# HVPulser0_3UCC21520.net
KiCad netlist of a schematic drawn in EAGLE
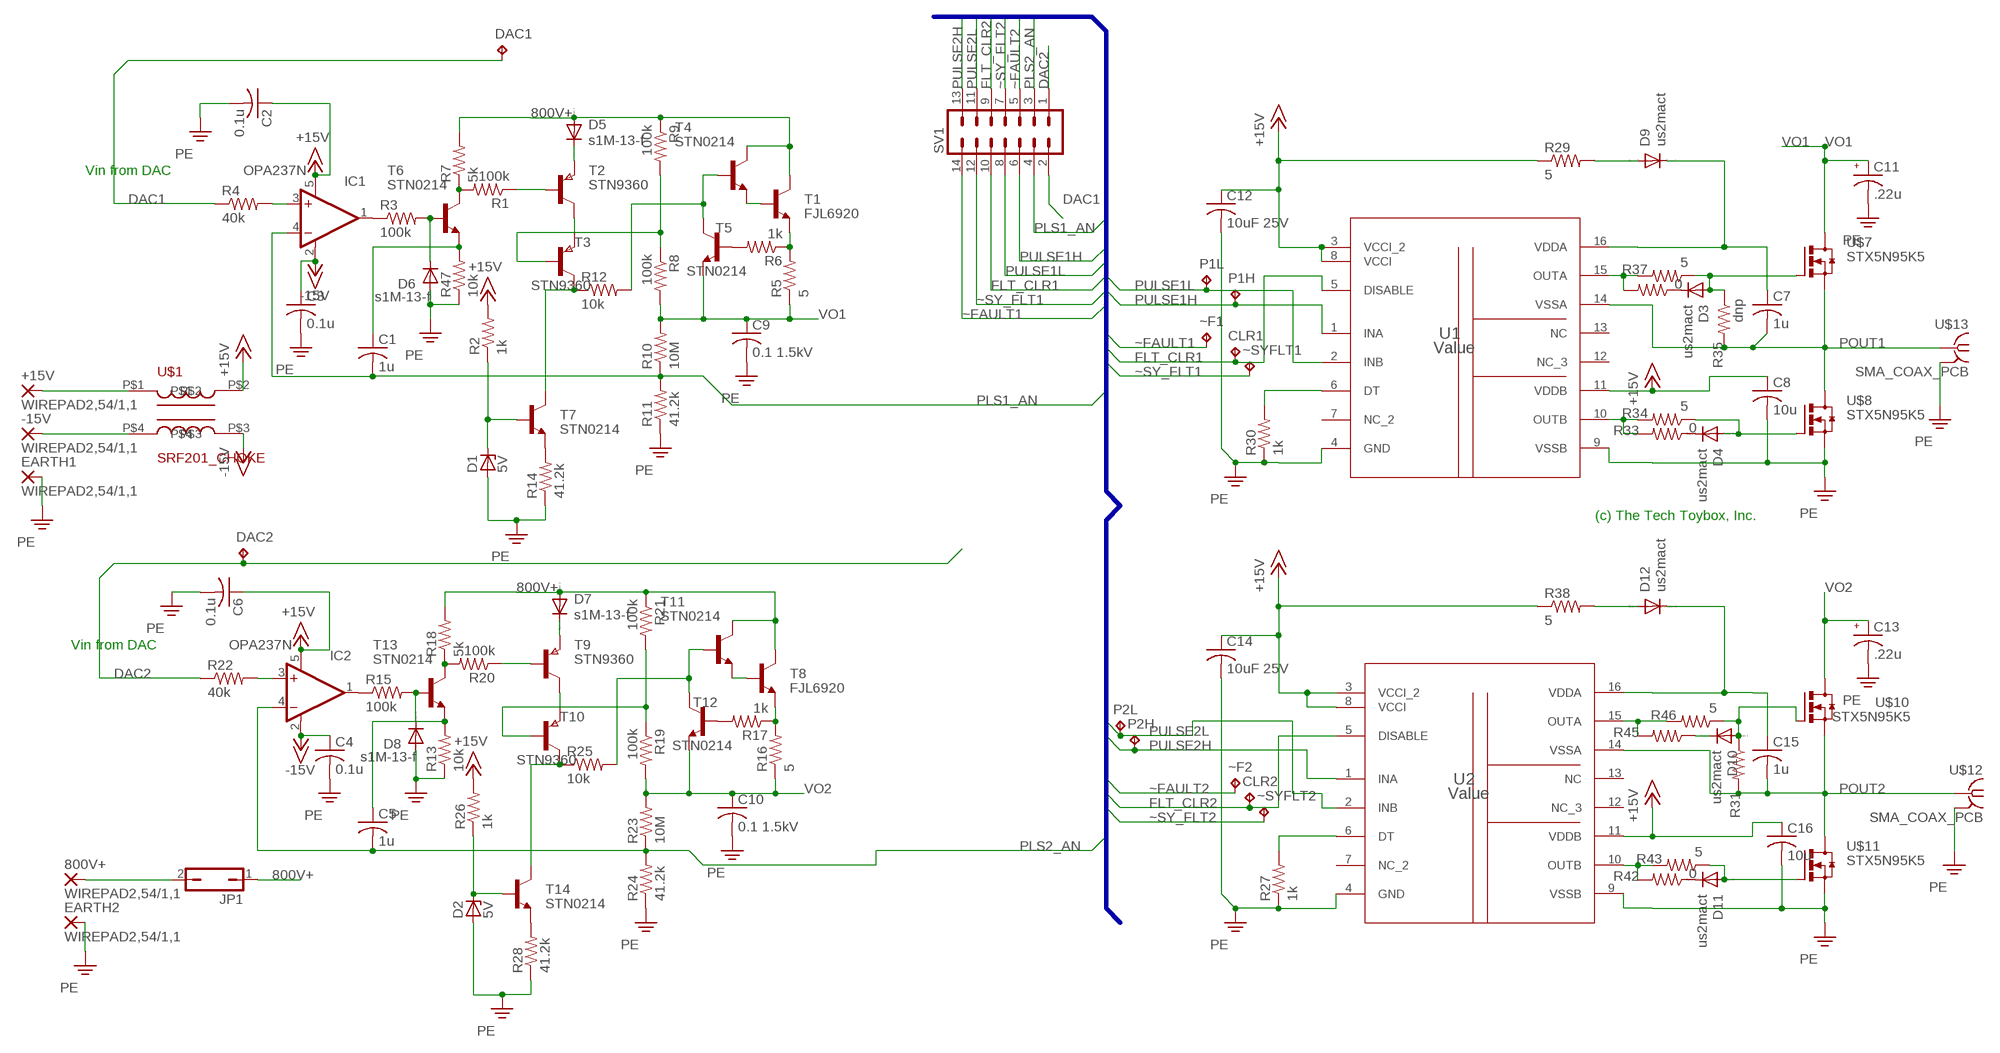
[diagram p0: schematic, sheet 1]

(export (version "E")
  (design (tool "Eeschema 10.0.6"))
  (components
    (comp (ref "+15V")
      (value "WIREPAD2,54/1,1")
      (footprint "eagle-import:2,54_1,1")
      (libsource (lib "eagle-import") (part "WIREPAD2,54/1,1"))
    )
    (comp (ref "-15V")
      (value "WIREPAD2,54/1,1")
      (footprint "eagle-import:2,54_1,1")
      (libsource (lib "eagle-import") (part "WIREPAD2,54/1,1"))
    )
    (comp (ref "800V+")
      (value "WIREPAD2,54/1,1")
      (footprint "eagle-import:2,54_1,1")
      (libsource (lib "eagle-import") (part "WIREPAD2,54/1,1"))
    )
    (comp (ref "C1")
      (value "1u")
      (footprint "eagle-import:C0805")
      (libsource (lib "eagle-import") (part "rcl_C-USC0805"))
    )
    (comp (ref "C2")
      (value "0.1u")
      (footprint "eagle-import:C0805")
      (libsource (lib "eagle-import") (part "rcl_C-USC0805"))
    )
    (comp (ref "C3")
      (value "0.1u")
      (footprint "eagle-import:C0805")
      (libsource (lib "eagle-import") (part "rcl_C-USC0805"))
    )
    (comp (ref "C4")
      (value "0.1u")
      (footprint "eagle-import:C0805")
      (libsource (lib "eagle-import") (part "rcl_C-USC0805"))
    )
    (comp (ref "C5")
      (value "1u")
      (footprint "eagle-import:C0805")
      (libsource (lib "eagle-import") (part "rcl_C-USC0805"))
    )
    (comp (ref "C6")
      (value "0.1u")
      (footprint "eagle-import:C0805")
      (libsource (lib "eagle-import") (part "rcl_C-USC0805"))
    )
    (comp (ref "C7")
      (value "1u")
      (footprint "eagle-import:C0805")
      (libsource (lib "eagle-import") (part "rcl_C-USC0805"))
    )
    (comp (ref "C8")
      (value "10u")
      (footprint "eagle-import:C1210")
      (libsource (lib "eagle-import") (part "rcl_C-USC1210"))
    )
    (comp (ref "C9")
      (value "0.1 1.5kV")
      (footprint "eagle-import:C2225K")
      (libsource (lib "eagle-import") (part "rcl_C-USC2225K"))
    )
    (comp (ref "C10")
      (value "0.1 1.5kV")
      (footprint "eagle-import:C2225K")
      (libsource (lib "eagle-import") (part "rcl_C-USC2225K"))
    )
    (comp (ref "C11")
      (value ".22u")
      (footprint "eagle-import:C050-035X075")
      (fields (field (name "PARTNO") "C1608X7R1H224K080AB"))
      (libsource (lib "eagle-import") (part "C-US050-035X075"))
    )
    (comp (ref "C12")
      (value "10uF 25V")
      (footprint "eagle-import:C0805")
      (libsource (lib "eagle-import") (part "rcl_C-USC0805"))
    )
    (comp (ref "C13")
      (value ".22u")
      (footprint "eagle-import:C050-035X075")
      (fields (field (name "PARTNO") "C1608X7R1H224K080AB"))
      (libsource (lib "eagle-import") (part "C-US050-035X075"))
    )
    (comp (ref "C14")
      (value "10uF 25V")
      (footprint "eagle-import:C0805")
      (libsource (lib "eagle-import") (part "rcl_C-USC0805"))
    )
    (comp (ref "C15")
      (value "1u")
      (footprint "eagle-import:C0805")
      (libsource (lib "eagle-import") (part "rcl_C-USC0805"))
    )
    (comp (ref "C16")
      (value "10u")
      (footprint "eagle-import:C1210")
      (libsource (lib "eagle-import") (part "rcl_C-USC1210"))
    )
    (comp (ref "CLR1")
      (value "TPTP10R")
      (footprint "eagle-import:TP10R")
      (libsource (lib "eagle-import") (part "TPTP10R"))
    )
    (comp (ref "CLR2")
      (value "TPTP10R")
      (footprint "eagle-import:TP10R")
      (libsource (lib "eagle-import") (part "TPTP10R"))
    )
    (comp (ref "D1")
      (value "5V")
      (footprint "eagle-import:DO41Z10")
      (libsource (lib "eagle-import") (part "ZENER-DIODEDO41Z10"))
    )
    (comp (ref "D2")
      (value "5V")
      (footprint "eagle-import:DO41Z10")
      (libsource (lib "eagle-import") (part "ZENER-DIODEDO41Z10"))
    )
    (comp (ref "D3")
      (value "us2mact")
      (footprint "eagle-import:DO214AC")
      (libsource (lib "eagle-import") (part "DIODE-DO214AC"))
    )
    (comp (ref "D4")
      (value "us2mact")
      (footprint "eagle-import:DO214AC")
      (libsource (lib "eagle-import") (part "DIODE-DO214AC"))
    )
    (comp (ref "D5")
      (value "s1M-13-f")
      (footprint "eagle-import:DO214AC")
      (libsource (lib "eagle-import") (part "DIODE-DO214AC"))
    )
    (comp (ref "D6")
      (value "s1M-13-f")
      (footprint "eagle-import:DO214AC")
      (libsource (lib "eagle-import") (part "DIODE-DO214AC"))
    )
    (comp (ref "D7")
      (value "s1M-13-f")
      (footprint "eagle-import:DO214AC")
      (libsource (lib "eagle-import") (part "DIODE-DO214AC"))
    )
    (comp (ref "D8")
      (value "s1M-13-f")
      (footprint "eagle-import:DO214AC")
      (libsource (lib "eagle-import") (part "DIODE-DO214AC"))
    )
    (comp (ref "D9")
      (value "us2mact")
      (footprint "eagle-import:DO214AC")
      (libsource (lib "eagle-import") (part "DIODE-DO214AC"))
    )
    (comp (ref "D10")
      (value "us2mact")
      (footprint "eagle-import:DO214AC")
      (libsource (lib "eagle-import") (part "DIODE-DO214AC"))
    )
    (comp (ref "D11")
      (value "us2mact")
      (footprint "eagle-import:DO214AC")
      (libsource (lib "eagle-import") (part "DIODE-DO214AC"))
    )
    (comp (ref "D12")
      (value "us2mact")
      (footprint "eagle-import:DO214AC")
      (libsource (lib "eagle-import") (part "DIODE-DO214AC"))
    )
    (comp (ref "DAC1")
      (value "TPTP10R")
      (footprint "eagle-import:TP10R")
      (libsource (lib "eagle-import") (part "TPTP10R"))
    )
    (comp (ref "DAC2")
      (value "TPTP10R")
      (footprint "eagle-import:TP10R")
      (libsource (lib "eagle-import") (part "TPTP10R"))
    )
    (comp (ref "EARTH1")
      (value "WIREPAD2,54/1,1")
      (footprint "eagle-import:2,54_1,1")
      (libsource (lib "eagle-import") (part "WIREPAD2,54/1,1"))
    )
    (comp (ref "EARTH2")
      (value "WIREPAD2,54/1,1")
      (footprint "eagle-import:2,54_1,1")
      (libsource (lib "eagle-import") (part "WIREPAD2,54/1,1"))
    )
    (comp (ref "IC1")
      (value "OPA237N")
      (footprint "eagle-import:SOT23-5")
      (fields (field (name "MF") "TEXAS INSTRUMENTS") (field (name "MPN") "OPA237NA/250"))
      (libsource (lib "eagle-import") (part "OPA237N"))
    )
    (comp (ref "IC2")
      (value "OPA237N")
      (footprint "eagle-import:SOT23-5")
      (fields (field (name "MF") "TEXAS INSTRUMENTS") (field (name "MPN") "OPA237NA/250"))
      (libsource (lib "eagle-import") (part "OPA237N"))
    )
    (comp (ref "JP1")
      (value "JP1Q")
      (footprint "eagle-import:JP1")
      (libsource (lib "eagle-import") (part "JP1Q"))
    )
    (comp (ref "P1H")
      (value "TPTP10R")
      (footprint "eagle-import:TP10R")
      (libsource (lib "eagle-import") (part "TPTP10R"))
    )
    (comp (ref "P1L")
      (value "TPTP10R")
      (footprint "eagle-import:TP10R")
      (libsource (lib "eagle-import") (part "TPTP10R"))
    )
    (comp (ref "P2H")
      (value "TPTP10R")
      (footprint "eagle-import:TP10R")
      (libsource (lib "eagle-import") (part "TPTP10R"))
    )
    (comp (ref "P2L")
      (value "TPTP10R")
      (footprint "eagle-import:TP10R")
      (libsource (lib "eagle-import") (part "TPTP10R"))
    )
    (comp (ref "R1")
      (value "100k")
      (footprint "eagle-import:P0613_15")
      (libsource (lib "eagle-import") (part "R-US_0613/15"))
    )
    (comp (ref "R2")
      (value "1k")
      (footprint "eagle-import:P0613_15")
      (libsource (lib "eagle-import") (part "R-US_0613/15"))
    )
    (comp (ref "R3")
      (value "100k")
      (footprint "eagle-import:R0603")
      (libsource (lib "eagle-import") (part "R-US_R0603"))
    )
    (comp (ref "R4")
      (value "40k")
      (footprint "eagle-import:R0603")
      (libsource (lib "eagle-import") (part "R-US_R0603"))
    )
    (comp (ref "R5")
      (value "5")
      (footprint "eagle-import:P0613_15")
      (libsource (lib "eagle-import") (part "R-US_0613/15"))
    )
    (comp (ref "R6")
      (value "1k")
      (footprint "eagle-import:P0613_15")
      (libsource (lib "eagle-import") (part "R-US_0613/15"))
    )
    (comp (ref "R7")
      (value "5k")
      (footprint "eagle-import:R0603")
      (libsource (lib "eagle-import") (part "R-US_R0603"))
    )
    (comp (ref "R8")
      (value "100k")
      (footprint "eagle-import:P0613_15")
      (libsource (lib "eagle-import") (part "R-US_0613/15"))
    )
    (comp (ref "R9")
      (value "100k")
      (footprint "eagle-import:P0613_15")
      (libsource (lib "eagle-import") (part "R-US_0613/15"))
    )
    (comp (ref "R10")
      (value "10M")
      (footprint "eagle-import:P0613_15")
      (libsource (lib "eagle-import") (part "R-US_0613/15"))
    )
    (comp (ref "R11")
      (value "41.2k")
      (footprint "eagle-import:P0613_15")
      (libsource (lib "eagle-import") (part "R-US_0613/15"))
    )
    (comp (ref "R12")
      (value "10k")
      (footprint "eagle-import:R0603")
      (libsource (lib "eagle-import") (part "R-US_R0603"))
    )
    (comp (ref "R13")
      (value "10k")
      (footprint "eagle-import:R0805")
      (libsource (lib "eagle-import") (part "R-US_R0805"))
    )
    (comp (ref "R14")
      (value "41.2k")
      (footprint "eagle-import:P0613_15")
      (libsource (lib "eagle-import") (part "R-US_0613/15"))
    )
    (comp (ref "R15")
      (value "100k")
      (footprint "eagle-import:R0603")
      (libsource (lib "eagle-import") (part "R-US_R0603"))
    )
    (comp (ref "R16")
      (value "5")
      (footprint "eagle-import:P0613_15")
      (libsource (lib "eagle-import") (part "R-US_0613/15"))
    )
    (comp (ref "R17")
      (value "1k")
      (footprint "eagle-import:P0613_15")
      (libsource (lib "eagle-import") (part "R-US_0613/15"))
    )
    (comp (ref "R18")
      (value "5k")
      (footprint "eagle-import:R0603")
      (libsource (lib "eagle-import") (part "R-US_R0603"))
    )
    (comp (ref "R19")
      (value "100k")
      (footprint "eagle-import:P0613_15")
      (libsource (lib "eagle-import") (part "R-US_0613/15"))
    )
    (comp (ref "R20")
      (value "100k")
      (footprint "eagle-import:P0613_15")
      (libsource (lib "eagle-import") (part "R-US_0613/15"))
    )
    (comp (ref "R21")
      (value "100k")
      (footprint "eagle-import:P0613_15")
      (libsource (lib "eagle-import") (part "R-US_0613/15"))
    )
    (comp (ref "R22")
      (value "40k")
      (footprint "eagle-import:R0603")
      (libsource (lib "eagle-import") (part "R-US_R0603"))
    )
    (comp (ref "R23")
      (value "10M")
      (footprint "eagle-import:P0613_15")
      (libsource (lib "eagle-import") (part "R-US_0613/15"))
    )
    (comp (ref "R24")
      (value "41.2k")
      (footprint "eagle-import:P0613_15")
      (libsource (lib "eagle-import") (part "R-US_0613/15"))
    )
    (comp (ref "R25")
      (value "10k")
      (footprint "eagle-import:R0603")
      (libsource (lib "eagle-import") (part "R-US_R0603"))
    )
    (comp (ref "R26")
      (value "1k")
      (footprint "eagle-import:P0613_15")
      (libsource (lib "eagle-import") (part "R-US_0613/15"))
    )
    (comp (ref "R27")
      (value "1k")
      (footprint "eagle-import:R0805")
      (libsource (lib "eagle-import") (part "R-US_R0805"))
    )
    (comp (ref "R28")
      (value "41.2k")
      (footprint "eagle-import:P0613_15")
      (libsource (lib "eagle-import") (part "R-US_0613/15"))
    )
    (comp (ref "R29")
      (value "5")
      (footprint "eagle-import:0207_10")
      (libsource (lib "eagle-import") (part "R-US_0207/10"))
    )
    (comp (ref "R30")
      (value "1k")
      (footprint "eagle-import:R0805")
      (libsource (lib "eagle-import") (part "R-US_R0805"))
    )
    (comp (ref "R31")
      (value "15")
      (footprint "eagle-import:R0805")
      (libsource (lib "eagle-import") (part "R-US_R0805"))
    )
    (comp (ref "R33")
      (value "0")
      (footprint "eagle-import:R0805")
      (libsource (lib "eagle-import") (part "R-US_R0805"))
    )
    (comp (ref "R34")
      (value "5")
      (footprint "eagle-import:R0805")
      (libsource (lib "eagle-import") (part "R-US_R0805"))
    )
    (comp (ref "R35")
      (value "dnp")
      (footprint "eagle-import:R0805")
      (libsource (lib "eagle-import") (part "R-US_R0805"))
    )
    (comp (ref "R36")
      (value "0")
      (footprint "eagle-import:R0805")
      (libsource (lib "eagle-import") (part "R-US_R0805"))
    )
    (comp (ref "R37")
      (value "5")
      (footprint "eagle-import:R0805")
      (libsource (lib "eagle-import") (part "R-US_R0805"))
    )
    (comp (ref "R38")
      (value "5")
      (footprint "eagle-import:0207_10")
      (libsource (lib "eagle-import") (part "R-US_0207/10"))
    )
    (comp (ref "R42")
      (value "0")
      (footprint "eagle-import:R0805")
      (libsource (lib "eagle-import") (part "R-US_R0805"))
    )
    (comp (ref "R43")
      (value "5")
      (footprint "eagle-import:R0805")
      (libsource (lib "eagle-import") (part "R-US_R0805"))
    )
    (comp (ref "R45")
      (value "15")
      (footprint "eagle-import:R0805")
      (libsource (lib "eagle-import") (part "R-US_R0805"))
    )
    (comp (ref "R46")
      (value "5")
      (footprint "eagle-import:R0805")
      (libsource (lib "eagle-import") (part "R-US_R0805"))
    )
    (comp (ref "R47")
      (value "10k")
      (footprint "eagle-import:R0805")
      (libsource (lib "eagle-import") (part "R-US_R0805"))
    )
    (comp (ref "SV1")
      (value "MA07-2")
      (footprint "eagle-import:MA07-2")
      (libsource (lib "eagle-import") (part "MA07-2"))
    )
    (comp (ref "T1")
      (value "FJL6920")
      (footprint "eagle-import:TO264V")
      (libsource (lib "eagle-import") (part "FJL6920-NPN_POWER"))
    )
    (comp (ref "T2")
      (value "STN9360")
      (footprint "eagle-import:SOT223")
      (fields (field (name "MPN") "DJT4030P-13"))
      (libsource (lib "eagle-import") (part "PNPSOT223"))
    )
    (comp (ref "T3")
      (value "STN9360")
      (footprint "eagle-import:SOT223")
      (fields (field (name "MPN") "DJT4030P-13"))
      (libsource (lib "eagle-import") (part "PNPSOT223"))
    )
    (comp (ref "T4")
      (value "STN0214")
      (footprint "eagle-import:SOT223")
      (libsource (lib "eagle-import") (part "-NPN-SOT223"))
    )
    (comp (ref "T5")
      (value "STN0214")
      (footprint "eagle-import:SOT223")
      (libsource (lib "eagle-import") (part "-NPN-SOT223"))
    )
    (comp (ref "T6")
      (value "STN0214")
      (footprint "eagle-import:SOT223")
      (libsource (lib "eagle-import") (part "-NPN-SOT223"))
    )
    (comp (ref "T7")
      (value "STN0214")
      (footprint "eagle-import:SOT223")
      (libsource (lib "eagle-import") (part "-NPN-SOT223"))
    )
    (comp (ref "T8")
      (value "FJL6920")
      (footprint "eagle-import:TO264V")
      (libsource (lib "eagle-import") (part "FJL6920-NPN_POWER"))
    )
    (comp (ref "T9")
      (value "STN9360")
      (footprint "eagle-import:SOT223")
      (fields (field (name "MPN") "DJT4030P-13"))
      (libsource (lib "eagle-import") (part "PNPSOT223"))
    )
    (comp (ref "T10")
      (value "STN9360")
      (footprint "eagle-import:SOT223")
      (fields (field (name "MPN") "DJT4030P-13"))
      (libsource (lib "eagle-import") (part "PNPSOT223"))
    )
    (comp (ref "T11")
      (value "STN0214")
      (footprint "eagle-import:SOT223")
      (libsource (lib "eagle-import") (part "-NPN-SOT223"))
    )
    (comp (ref "T12")
      (value "STN0214")
      (footprint "eagle-import:SOT223")
      (libsource (lib "eagle-import") (part "-NPN-SOT223"))
    )
    (comp (ref "T13")
      (value "STN0214")
      (footprint "eagle-import:SOT223")
      (libsource (lib "eagle-import") (part "-NPN-SOT223"))
    )
    (comp (ref "T14")
      (value "STN0214")
      (footprint "eagle-import:SOT223")
      (libsource (lib "eagle-import") (part "-NPN-SOT223"))
    )
    (comp (ref "U$1")
      (value "SRF201_CHOKE")
      (footprint "eagle-import:CHOKE_BOURNES_SRF2012")
      (libsource (lib "eagle-import") (part "SRF201_CHOKE"))
    )
    (comp (ref "U$7")
      (value "STX5N95K5")
      (footprint "eagle-import:TO220AV")
      (libsource (lib "eagle-import") (part "STX5N95K5"))
    )
    (comp (ref "U$8")
      (value "STX5N95K5")
      (footprint "eagle-import:TO220AV")
      (libsource (lib "eagle-import") (part "STX5N95K5"))
    )
    (comp (ref "U$10")
      (value "STX5N95K5")
      (footprint "eagle-import:TO220AV")
      (libsource (lib "eagle-import") (part "STX5N95K5"))
    )
    (comp (ref "U$11")
      (value "STX5N95K5")
      (footprint "eagle-import:TO220AV")
      (libsource (lib "eagle-import") (part "STX5N95K5"))
    )
    (comp (ref "U$12")
      (value "SMA_COAX_PCB")
      (footprint "eagle-import:SMA-COAX-V-TECONNECT")
      (libsource (lib "eagle-import") (part "SMA_COAX_PCB"))
    )
    (comp (ref "U$13")
      (value "SMA_COAX_PCB")
      (footprint "eagle-import:SMA-COAX-V-TECONNECT")
      (libsource (lib "eagle-import") (part "SMA_COAX_PCB"))
    )
    (comp (ref "U1")
      (value "Value")
      (footprint "eagle-import:DW0016A_N")
      (fields (field (name "MANUFACTURER") "Texas Instruments") (field (name "PARTNUMBER") "UCC21520ADWR"))
      (libsource (lib "eagle-import") (part "UCC21520ADWR"))
    )
    (comp (ref "U2")
      (value "Value")
      (footprint "eagle-import:DW0016A_N")
      (fields (field (name "MANUFACTURER") "Texas Instruments") (field (name "PARTNUMBER") "UCC21520ADWR"))
      (libsource (lib "eagle-import") (part "UCC21520ADWR"))
    )
    (comp (ref "~F1")
      (value "TPTP10R")
      (footprint "eagle-import:TP10R")
      (libsource (lib "eagle-import") (part "TPTP10R"))
    )
    (comp (ref "~F2")
      (value "TPTP10R")
      (footprint "eagle-import:TP10R")
      (libsource (lib "eagle-import") (part "TPTP10R"))
    )
    (comp (ref "~SYFLT1")
      (value "TPTP10R")
      (footprint "eagle-import:TP10R")
      (libsource (lib "eagle-import") (part "TPTP10R"))
    )
    (comp (ref "~SYFLT2")
      (value "TPTP10R")
      (footprint "eagle-import:TP10R")
      (libsource (lib "eagle-import") (part "TPTP10R"))
    )
  )
  (nets
    (net (code "1") (name "+15V") (class "Default")
      (node (ref "C12") (pin "1") (pinfunction "1_1") (pintype "passive"))
      (node (ref "C14") (pin "1") (pinfunction "1_1") (pintype "passive"))
      (node (ref "C16") (pin "1") (pinfunction "1_1") (pintype "passive"))
      (node (ref "C2") (pin "1") (pinfunction "1_1") (pintype "passive"))
      (node (ref "C6") (pin "1") (pinfunction "1_1") (pintype "passive"))
      (node (ref "C8") (pin "1") (pinfunction "1_1") (pintype "passive"))
      (node (ref "IC1") (pin "5") (pinfunction "V+_5") (pintype "power_in"))
      (node (ref "IC2") (pin "5") (pinfunction "V+_5") (pintype "power_in"))
      (node (ref "R2") (pin "2") (pinfunction "2_2") (pintype "passive"))
      (node (ref "R26") (pin "2") (pinfunction "2_2") (pintype "passive"))
      (node (ref "R29") (pin "1") (pinfunction "1_1") (pintype "passive"))
      (node (ref "R38") (pin "1") (pinfunction "1_1") (pintype "passive"))
      (node (ref "U$1") (pin "P$2") (pinfunction "P$2_P$2") (pintype "bidirectional"))
      (node (ref "U1") (pin "11") (pinfunction "VDDB_11") (pintype "power_in"))
      (node (ref "U1") (pin "3") (pinfunction "VCCI_2_3") (pintype "power_in"))
      (node (ref "U1") (pin "8") (pinfunction "VCCI_8") (pintype "power_in"))
      (node (ref "U2") (pin "11") (pinfunction "VDDB_11") (pintype "power_in"))
      (node (ref "U2") (pin "3") (pinfunction "VCCI_2_3") (pintype "power_in"))
      (node (ref "U2") (pin "8") (pinfunction "VCCI_8") (pintype "power_in"))
    )
    (net (code "2") (name "-15V") (class "Default")
      (node (ref "C3") (pin "1") (pinfunction "1_1") (pintype "passive"))
      (node (ref "C4") (pin "1") (pinfunction "1_1") (pintype "passive"))
      (node (ref "IC1") (pin "2") (pinfunction "V-_2") (pintype "power_in"))
      (node (ref "IC2") (pin "2") (pinfunction "V-_2") (pintype "power_in"))
      (node (ref "U$1") (pin "P$3") (pinfunction "P$3_P$3") (pintype "bidirectional"))
    )
    (net (code "3") (name "/800V+") (class "Default")
      (node (ref "D5") (pin "A") (pinfunction "A_A") (pintype "passive"))
      (node (ref "D7") (pin "A") (pinfunction "A_A") (pintype "passive"))
      (node (ref "JP1") (pin "1") (pinfunction "1_1") (pintype "passive"))
      (node (ref "R18") (pin "2") (pinfunction "2_2") (pintype "passive"))
      (node (ref "R21") (pin "1") (pinfunction "1_1") (pintype "passive"))
      (node (ref "R7") (pin "2") (pinfunction "2_2") (pintype "passive"))
      (node (ref "R9") (pin "1") (pinfunction "1_1") (pintype "passive"))
      (node (ref "T1") (pin "2") (pinfunction "C_2") (pintype "passive"))
      (node (ref "T11") (pin "4") (pinfunction "C_4") (pintype "passive"))
      (node (ref "T4") (pin "4") (pinfunction "C_4") (pintype "passive"))
      (node (ref "T8") (pin "2") (pinfunction "C_2") (pintype "passive"))
    )
    (net (code "4") (name "/DAC1") (class "Default")
      (node (ref "DAC1") (pin "TP") (pinfunction "TP_TP") (pintype "input"))
      (node (ref "R4") (pin "1") (pinfunction "1_1") (pintype "passive"))
      (node (ref "SV1") (pin "2") (pinfunction "2_2") (pintype "passive"))
    )
    (net (code "5") (name "/DAC2") (class "Default")
      (node (ref "DAC2") (pin "TP") (pinfunction "TP_TP") (pintype "input"))
      (node (ref "R22") (pin "1") (pinfunction "1_1") (pintype "passive"))
      (node (ref "SV1") (pin "1") (pinfunction "1_1") (pintype "passive"))
    )
    (net (code "6") (name "/FLT_CLR1") (class "Default")
      (node (ref "CLR1") (pin "TP") (pinfunction "TP_TP") (pintype "input"))
      (node (ref "SV1") (pin "10") (pinfunction "10_10") (pintype "passive"))
      (node (ref "U1") (pin "5") (pinfunction "DISABLE_5") (pintype "input"))
    )
    (net (code "7") (name "/FLT_CLR2") (class "Default")
      (node (ref "CLR2") (pin "TP") (pinfunction "TP_TP") (pintype "input"))
      (node (ref "SV1") (pin "9") (pinfunction "9_9") (pintype "passive"))
      (node (ref "U2") (pin "5") (pinfunction "DISABLE_5") (pintype "input"))
    )
    (net (code "8") (name "/PLS1_AN") (class "Default")
      (node (ref "C1") (pin "2") (pinfunction "2_2") (pintype "passive"))
      (node (ref "IC1") (pin "4") (pinfunction "-IN_4") (pintype "input"))
      (node (ref "R10") (pin "1") (pinfunction "1_1") (pintype "passive"))
      (node (ref "R11") (pin "2") (pinfunction "2_2") (pintype "passive"))
      (node (ref "SV1") (pin "4") (pinfunction "4_4") (pintype "passive"))
    )
    (net (code "9") (name "/PLS2_AN") (class "Default")
      (node (ref "C5") (pin "2") (pinfunction "2_2") (pintype "passive"))
      (node (ref "IC2") (pin "4") (pinfunction "-IN_4") (pintype "input"))
      (node (ref "R23") (pin "1") (pinfunction "1_1") (pintype "passive"))
      (node (ref "R24") (pin "2") (pinfunction "2_2") (pintype "passive"))
      (node (ref "SV1") (pin "3") (pinfunction "3_3") (pintype "passive"))
    )
    (net (code "10") (name "/POUT1") (class "Default")
      (node (ref "C7") (pin "2") (pinfunction "2_2") (pintype "passive"))
      (node (ref "R35") (pin "2") (pinfunction "2_2") (pintype "passive"))
      (node (ref "U$13") (pin "1") (pinfunction "1_1") (pintype "passive"))
      (node (ref "U$7") (pin "3") (pinfunction "S_3") (pintype "passive"))
      (node (ref "U$8") (pin "2") (pinfunction "D_2") (pintype "passive"))
      (node (ref "U1") (pin "14") (pinfunction "VSSA_14") (pintype "power_in"))
    )
    (net (code "11") (name "/POUT2") (class "Default")
      (node (ref "C15") (pin "2") (pinfunction "2_2") (pintype "passive"))
      (node (ref "R31") (pin "2") (pinfunction "2_2") (pintype "passive"))
      (node (ref "U$10") (pin "3") (pinfunction "S_3") (pintype "passive"))
      (node (ref "U$11") (pin "2") (pinfunction "D_2") (pintype "passive"))
      (node (ref "U$12") (pin "1") (pinfunction "1_1") (pintype "passive"))
      (node (ref "U2") (pin "14") (pinfunction "VSSA_14") (pintype "power_in"))
    )
    (net (code "12") (name "/PULSE1H") (class "Default")
      (node (ref "P1H") (pin "TP") (pinfunction "TP_TP") (pintype "input"))
      (node (ref "SV1") (pin "6") (pinfunction "6_6") (pintype "passive"))
      (node (ref "U1") (pin "1") (pinfunction "INA_1") (pintype "input"))
    )
    (net (code "13") (name "/PULSE1L") (class "Default")
      (node (ref "P1L") (pin "TP") (pinfunction "TP_TP") (pintype "input"))
      (node (ref "SV1") (pin "8") (pinfunction "8_8") (pintype "passive"))
      (node (ref "U1") (pin "2") (pinfunction "INB_2") (pintype "passive"))
    )
    (net (code "14") (name "/PULSE2H") (class "Default")
      (node (ref "P2H") (pin "TP") (pinfunction "TP_TP") (pintype "input"))
      (node (ref "SV1") (pin "13") (pinfunction "13_13") (pintype "passive"))
      (node (ref "U2") (pin "1") (pinfunction "INA_1") (pintype "input"))
    )
    (net (code "15") (name "/PULSE2L") (class "Default")
      (node (ref "P2L") (pin "TP") (pinfunction "TP_TP") (pintype "input"))
      (node (ref "SV1") (pin "11") (pinfunction "11_11") (pintype "passive"))
      (node (ref "U2") (pin "2") (pinfunction "INB_2") (pintype "passive"))
    )
    (net (code "16") (name "/VO1") (class "Default")
      (node (ref "C11") (pin "1") (pinfunction "1_1") (pintype "passive"))
      (node (ref "C9") (pin "1") (pinfunction "1_1") (pintype "passive"))
      (node (ref "R10") (pin "2") (pinfunction "2_2") (pintype "passive"))
      (node (ref "R5") (pin "1") (pinfunction "1_1") (pintype "passive"))
      (node (ref "R8") (pin "2") (pinfunction "2_2") (pintype "passive"))
      (node (ref "T5") (pin "3") (pinfunction "E_3") (pintype "passive"))
      (node (ref "U$7") (pin "2") (pinfunction "D_2") (pintype "passive"))
    )
    (net (code "17") (name "/VO2") (class "Default")
      (node (ref "C10") (pin "1") (pinfunction "1_1") (pintype "passive"))
      (node (ref "C13") (pin "1") (pinfunction "1_1") (pintype "passive"))
      (node (ref "R16") (pin "1") (pinfunction "1_1") (pintype "passive"))
      (node (ref "R19") (pin "2") (pinfunction "2_2") (pintype "passive"))
      (node (ref "R23") (pin "2") (pinfunction "2_2") (pintype "passive"))
      (node (ref "T12") (pin "3") (pinfunction "E_3") (pintype "passive"))
      (node (ref "U$10") (pin "2") (pinfunction "D_2") (pintype "passive"))
    )
    (net (code "18") (name "/~{FAULT1}") (class "Default")
      (node (ref "SV1") (pin "14") (pinfunction "14_14") (pintype "passive"))
      (node (ref "~F1") (pin "TP") (pinfunction "TP_TP") (pintype "input"))
    )
    (net (code "19") (name "/~{FAULT2}") (class "Default")
      (node (ref "SV1") (pin "5") (pinfunction "5_5") (pintype "passive"))
      (node (ref "~F2") (pin "TP") (pinfunction "TP_TP") (pintype "input"))
    )
    (net (code "20") (name "/~{SY_FLT1}") (class "Default")
      (node (ref "SV1") (pin "12") (pinfunction "12_12") (pintype "passive"))
      (node (ref "~SYFLT1") (pin "TP") (pinfunction "TP_TP") (pintype "input"))
    )
    (net (code "21") (name "/~{SY_FLT2}") (class "Default")
      (node (ref "SV1") (pin "7") (pinfunction "7_7") (pintype "passive"))
      (node (ref "~SYFLT2") (pin "TP") (pinfunction "TP_TP") (pintype "input"))
    )
    (net (code "22") (name "Net-(+15V-P)") (class "Default")
      (node (ref "+15V") (pin "1") (pinfunction "P_1") (pintype "passive"))
      (node (ref "U$1") (pin "P$1") (pinfunction "P$1_P$1") (pintype "bidirectional"))
    )
    (net (code "23") (name "Net-(-15V-P)") (class "Default")
      (node (ref "-15V") (pin "1") (pinfunction "P_1") (pintype "passive"))
      (node (ref "U$1") (pin "P$4") (pinfunction "P$4_P$4") (pintype "bidirectional"))
    )
    (net (code "24") (name "Net-(800V+-P)") (class "Default")
      (node (ref "800V+") (pin "1") (pinfunction "P_1") (pintype "passive"))
      (node (ref "JP1") (pin "2") (pinfunction "2_2") (pintype "passive"))
    )
    (net (code "25") (name "Net-(D3-PadC)") (class "Default")
      (node (ref "D3") (pin "C") (pinfunction "C_C") (pintype "passive"))
      (node (ref "R36") (pin "1") (pinfunction "1_1") (pintype "passive"))
    )
    (net (code "26") (name "Net-(D4-PadC)") (class "Default")
      (node (ref "D4") (pin "C") (pinfunction "C_C") (pintype "passive"))
      (node (ref "R33") (pin "1") (pinfunction "1_1") (pintype "passive"))
    )
    (net (code "27") (name "Net-(D9-PadA)") (class "Default")
      (node (ref "D9") (pin "A") (pinfunction "A_A") (pintype "passive"))
      (node (ref "R29") (pin "2") (pinfunction "2_2") (pintype "passive"))
    )
    (net (code "28") (name "Net-(D10-PadC)") (class "Default")
      (node (ref "D10") (pin "C") (pinfunction "C_C") (pintype "passive"))
      (node (ref "R45") (pin "1") (pinfunction "1_1") (pintype "passive"))
    )
    (net (code "29") (name "Net-(D11-PadC)") (class "Default")
      (node (ref "D11") (pin "C") (pinfunction "C_C") (pintype "passive"))
      (node (ref "R42") (pin "1") (pinfunction "1_1") (pintype "passive"))
    )
    (net (code "30") (name "Net-(D12-PadA)") (class "Default")
      (node (ref "D12") (pin "A") (pinfunction "A_A") (pintype "passive"))
      (node (ref "R38") (pin "2") (pinfunction "2_2") (pintype "passive"))
    )
    (net (code "31") (name "Net-(IC1-+IN)") (class "Default")
      (node (ref "IC1") (pin "3") (pinfunction "+IN_3") (pintype "input"))
      (node (ref "R4") (pin "2") (pinfunction "2_2") (pintype "passive"))
    )
    (net (code "32") (name "Net-(IC1-OUT)") (class "Default")
      (node (ref "IC1") (pin "1") (pinfunction "OUT_1") (pintype "output"))
      (node (ref "R3") (pin "1") (pinfunction "1_1") (pintype "passive"))
    )
    (net (code "33") (name "Net-(IC2-+IN)") (class "Default")
      (node (ref "IC2") (pin "3") (pinfunction "+IN_3") (pintype "input"))
      (node (ref "R22") (pin "2") (pinfunction "2_2") (pintype "passive"))
    )
    (net (code "34") (name "Net-(IC2-OUT)") (class "Default")
      (node (ref "IC2") (pin "1") (pinfunction "OUT_1") (pintype "output"))
      (node (ref "R15") (pin "1") (pinfunction "1_1") (pintype "passive"))
    )
    (net (code "35") (name "Net-(T1-B)") (class "Default")
      (node (ref "T1") (pin "1") (pinfunction "B_1") (pintype "passive"))
      (node (ref "T4") (pin "3") (pinfunction "E_3") (pintype "passive"))
    )
    (net (code "36") (name "Net-(T1-E)") (class "Default")
      (node (ref "R5") (pin "2") (pinfunction "2_2") (pintype "passive"))
      (node (ref "R6") (pin "1") (pinfunction "1_1") (pintype "passive"))
      (node (ref "T1") (pin "3") (pinfunction "E_3") (pintype "passive"))
    )
    (net (code "37") (name "Net-(T2-B)") (class "Default")
      (node (ref "R1") (pin "1") (pinfunction "1_1") (pintype "passive"))
      (node (ref "T2") (pin "1") (pinfunction "B_1") (pintype "passive"))
    )
    (net (code "38") (name "Net-(T2-E)") (class "Default")
      (node (ref "D5") (pin "C") (pinfunction "C_C") (pintype "passive"))
      (node (ref "T2") (pin "3") (pinfunction "E_3") (pintype "passive"))
    )
    (net (code "39") (name "Net-(T3-B)") (class "Default")
      (node (ref "R8") (pin "1") (pinfunction "1_1") (pintype "passive"))
      (node (ref "R9") (pin "2") (pinfunction "2_2") (pintype "passive"))
      (node (ref "T3") (pin "1") (pinfunction "B_1") (pintype "passive"))
    )
    (net (code "40") (name "Net-(T3-E)") (class "Default")
      (node (ref "T2") (pin "2") (pinfunction "C_2") (pintype "passive"))
      (node (ref "T2") (pin "4") (pinfunction "C_4") (pintype "passive"))
      (node (ref "T3") (pin "3") (pinfunction "E_3") (pintype "passive"))
    )
    (net (code "41") (name "Net-(T4-B)") (class "Default")
      (node (ref "R12") (pin "2") (pinfunction "2_2") (pintype "passive"))
      (node (ref "T4") (pin "1") (pinfunction "B_1") (pintype "passive"))
      (node (ref "T5") (pin "4") (pinfunction "C_4") (pintype "passive"))
    )
    (net (code "42") (name "Net-(T5-B)") (class "Default")
      (node (ref "R6") (pin "2") (pinfunction "2_2") (pintype "passive"))
      (node (ref "T5") (pin "1") (pinfunction "B_1") (pintype "passive"))
    )
    (net (code "43") (name "Net-(T6-B)") (class "Default")
      (node (ref "D6") (pin "C") (pinfunction "C_C") (pintype "passive"))
      (node (ref "R3") (pin "2") (pinfunction "2_2") (pintype "passive"))
      (node (ref "T6") (pin "1") (pinfunction "B_1") (pintype "passive"))
    )
    (net (code "44") (name "Net-(T6-C)") (class "Default")
      (node (ref "R1") (pin "2") (pinfunction "2_2") (pintype "passive"))
      (node (ref "R7") (pin "1") (pinfunction "1_1") (pintype "passive"))
      (node (ref "T6") (pin "4") (pinfunction "C_4") (pintype "passive"))
    )
    (net (code "45") (name "Net-(T6-E)") (class "Default")
      (node (ref "C1") (pin "1") (pinfunction "1_1") (pintype "passive"))
      (node (ref "R47") (pin "2") (pinfunction "2_2") (pintype "passive"))
      (node (ref "T6") (pin "3") (pinfunction "E_3") (pintype "passive"))
    )
    (net (code "46") (name "Net-(T7-B)") (class "Default")
      (node (ref "D1") (pin "C") (pinfunction "C_C") (pintype "passive"))
      (node (ref "R2") (pin "1") (pinfunction "1_1") (pintype "passive"))
      (node (ref "T7") (pin "1") (pinfunction "B_1") (pintype "passive"))
    )
    (net (code "47") (name "Net-(T7-C)") (class "Default")
      (node (ref "R12") (pin "1") (pinfunction "1_1") (pintype "passive"))
      (node (ref "T3") (pin "2") (pinfunction "C_2") (pintype "passive"))
      (node (ref "T3") (pin "4") (pinfunction "C_4") (pintype "passive"))
      (node (ref "T7") (pin "4") (pinfunction "C_4") (pintype "passive"))
    )
    (net (code "48") (name "Net-(T7-E)") (class "Default")
      (node (ref "R14") (pin "2") (pinfunction "2_2") (pintype "passive"))
      (node (ref "T7") (pin "3") (pinfunction "E_3") (pintype "passive"))
    )
    (net (code "49") (name "Net-(T8-E)") (class "Default")
      (node (ref "R16") (pin "2") (pinfunction "2_2") (pintype "passive"))
      (node (ref "R17") (pin "1") (pinfunction "1_1") (pintype "passive"))
      (node (ref "T8") (pin "3") (pinfunction "E_3") (pintype "passive"))
    )
    (net (code "50") (name "Net-(T9-B)") (class "Default")
      (node (ref "R20") (pin "1") (pinfunction "1_1") (pintype "passive"))
      (node (ref "T9") (pin "1") (pinfunction "B_1") (pintype "passive"))
    )
    (net (code "51") (name "Net-(T9-E)") (class "Default")
      (node (ref "D7") (pin "C") (pinfunction "C_C") (pintype "passive"))
      (node (ref "T9") (pin "3") (pinfunction "E_3") (pintype "passive"))
    )
    (net (code "52") (name "Net-(T10-B)") (class "Default")
      (node (ref "R19") (pin "1") (pinfunction "1_1") (pintype "passive"))
      (node (ref "R21") (pin "2") (pinfunction "2_2") (pintype "passive"))
      (node (ref "T10") (pin "1") (pinfunction "B_1") (pintype "passive"))
    )
    (net (code "53") (name "Net-(T10-E)") (class "Default")
      (node (ref "T10") (pin "3") (pinfunction "E_3") (pintype "passive"))
      (node (ref "T9") (pin "2") (pinfunction "C_2") (pintype "passive"))
      (node (ref "T9") (pin "4") (pinfunction "C_4") (pintype "passive"))
    )
    (net (code "54") (name "Net-(T11-B)") (class "Default")
      (node (ref "R25") (pin "2") (pinfunction "2_2") (pintype "passive"))
      (node (ref "T11") (pin "1") (pinfunction "B_1") (pintype "passive"))
      (node (ref "T12") (pin "4") (pinfunction "C_4") (pintype "passive"))
    )
    (net (code "55") (name "Net-(T11-E)") (class "Default")
      (node (ref "T11") (pin "3") (pinfunction "E_3") (pintype "passive"))
      (node (ref "T8") (pin "1") (pinfunction "B_1") (pintype "passive"))
    )
    (net (code "56") (name "Net-(T12-B)") (class "Default")
      (node (ref "R17") (pin "2") (pinfunction "2_2") (pintype "passive"))
      (node (ref "T12") (pin "1") (pinfunction "B_1") (pintype "passive"))
    )
    (net (code "57") (name "Net-(T13-B)") (class "Default")
      (node (ref "D8") (pin "C") (pinfunction "C_C") (pintype "passive"))
      (node (ref "R15") (pin "2") (pinfunction "2_2") (pintype "passive"))
      (node (ref "T13") (pin "1") (pinfunction "B_1") (pintype "passive"))
    )
    (net (code "58") (name "Net-(T13-C)") (class "Default")
      (node (ref "R18") (pin "1") (pinfunction "1_1") (pintype "passive"))
      (node (ref "R20") (pin "2") (pinfunction "2_2") (pintype "passive"))
      (node (ref "T13") (pin "4") (pinfunction "C_4") (pintype "passive"))
    )
    (net (code "59") (name "Net-(T13-E)") (class "Default")
      (node (ref "C5") (pin "1") (pinfunction "1_1") (pintype "passive"))
      (node (ref "R13") (pin "2") (pinfunction "2_2") (pintype "passive"))
      (node (ref "T13") (pin "3") (pinfunction "E_3") (pintype "passive"))
    )
    (net (code "60") (name "Net-(T14-B)") (class "Default")
      (node (ref "D2") (pin "C") (pinfunction "C_C") (pintype "passive"))
      (node (ref "R26") (pin "1") (pinfunction "1_1") (pintype "passive"))
      (node (ref "T14") (pin "1") (pinfunction "B_1") (pintype "passive"))
    )
    (net (code "61") (name "Net-(T14-C)") (class "Default")
      (node (ref "R25") (pin "1") (pinfunction "1_1") (pintype "passive"))
      (node (ref "T10") (pin "2") (pinfunction "C_2") (pintype "passive"))
      (node (ref "T10") (pin "4") (pinfunction "C_4") (pintype "passive"))
      (node (ref "T14") (pin "4") (pinfunction "C_4") (pintype "passive"))
    )
    (net (code "62") (name "Net-(T14-E)") (class "Default")
      (node (ref "R28") (pin "2") (pinfunction "2_2") (pintype "passive"))
      (node (ref "T14") (pin "3") (pinfunction "E_3") (pintype "passive"))
    )
    (net (code "63") (name "Net-(U$7-G)") (class "Default")
      (node (ref "D3") (pin "A") (pinfunction "A_A") (pintype "passive"))
      (node (ref "R35") (pin "1") (pinfunction "1_1") (pintype "passive"))
      (node (ref "R37") (pin "1") (pinfunction "1_1") (pintype "passive"))
      (node (ref "U$7") (pin "1") (pinfunction "G_1") (pintype "passive"))
    )
    (net (code "64") (name "Net-(U$8-G)") (class "Default")
      (node (ref "D4") (pin "A") (pinfunction "A_A") (pintype "passive"))
      (node (ref "R34") (pin "1") (pinfunction "1_1") (pintype "passive"))
      (node (ref "U$8") (pin "1") (pinfunction "G_1") (pintype "passive"))
    )
    (net (code "65") (name "Net-(U$10-G)") (class "Default")
      (node (ref "D10") (pin "A") (pinfunction "A_A") (pintype "passive"))
      (node (ref "R31") (pin "1") (pinfunction "1_1") (pintype "passive"))
      (node (ref "R46") (pin "1") (pinfunction "1_1") (pintype "passive"))
      (node (ref "U$10") (pin "1") (pinfunction "G_1") (pintype "passive"))
    )
    (net (code "66") (name "Net-(U$11-G)") (class "Default")
      (node (ref "D11") (pin "A") (pinfunction "A_A") (pintype "passive"))
      (node (ref "R43") (pin "1") (pinfunction "1_1") (pintype "passive"))
      (node (ref "U$11") (pin "1") (pinfunction "G_1") (pintype "passive"))
    )
    (net (code "67") (name "Net-(U1-DT)") (class "Default")
      (node (ref "R30") (pin "2") (pinfunction "2_2") (pintype "passive"))
      (node (ref "U1") (pin "6") (pinfunction "DT_6") (pintype "input"))
    )
    (net (code "68") (name "Net-(U1-OUTA)") (class "Default")
      (node (ref "R36") (pin "2") (pinfunction "2_2") (pintype "passive"))
      (node (ref "R37") (pin "2") (pinfunction "2_2") (pintype "passive"))
      (node (ref "U1") (pin "15") (pinfunction "OUTA_15") (pintype "output"))
    )
    (net (code "69") (name "Net-(U1-OUTB)") (class "Default")
      (node (ref "R33") (pin "2") (pinfunction "2_2") (pintype "passive"))
      (node (ref "R34") (pin "2") (pinfunction "2_2") (pintype "passive"))
      (node (ref "U1") (pin "10") (pinfunction "OUTB_10") (pintype "output"))
    )
    (net (code "70") (name "Net-(U1-VDDA)") (class "Default")
      (node (ref "C7") (pin "1") (pinfunction "1_1") (pintype "passive"))
      (node (ref "D9") (pin "C") (pinfunction "C_C") (pintype "passive"))
      (node (ref "U1") (pin "16") (pinfunction "VDDA_16") (pintype "power_in"))
    )
    (net (code "71") (name "Net-(U2-DT)") (class "Default")
      (node (ref "R27") (pin "2") (pinfunction "2_2") (pintype "passive"))
      (node (ref "U2") (pin "6") (pinfunction "DT_6") (pintype "input"))
    )
    (net (code "72") (name "Net-(U2-OUTA)") (class "Default")
      (node (ref "R45") (pin "2") (pinfunction "2_2") (pintype "passive"))
      (node (ref "R46") (pin "2") (pinfunction "2_2") (pintype "passive"))
      (node (ref "U2") (pin "15") (pinfunction "OUTA_15") (pintype "output"))
    )
    (net (code "73") (name "Net-(U2-OUTB)") (class "Default")
      (node (ref "R42") (pin "2") (pinfunction "2_2") (pintype "passive"))
      (node (ref "R43") (pin "2") (pinfunction "2_2") (pintype "passive"))
      (node (ref "U2") (pin "10") (pinfunction "OUTB_10") (pintype "output"))
    )
    (net (code "74") (name "Net-(U2-VDDA)") (class "Default")
      (node (ref "C15") (pin "1") (pinfunction "1_1") (pintype "passive"))
      (node (ref "D12") (pin "C") (pinfunction "C_C") (pintype "passive"))
      (node (ref "U2") (pin "16") (pinfunction "VDDA_16") (pintype "power_in"))
    )
    (net (code "75") (name "PE") (class "Default")
      (node (ref "C10") (pin "2") (pinfunction "2_2") (pintype "passive"))
      (node (ref "C11") (pin "2") (pinfunction "2_2") (pintype "passive"))
      (node (ref "C12") (pin "2") (pinfunction "2_2") (pintype "passive"))
      (node (ref "C13") (pin "2") (pinfunction "2_2") (pintype "passive"))
      (node (ref "C14") (pin "2") (pinfunction "2_2") (pintype "passive"))
      (node (ref "C16") (pin "2") (pinfunction "2_2") (pintype "passive"))
      (node (ref "C2") (pin "2") (pinfunction "2_2") (pintype "passive"))
      (node (ref "C3") (pin "2") (pinfunction "2_2") (pintype "passive"))
      (node (ref "C4") (pin "2") (pinfunction "2_2") (pintype "passive"))
      (node (ref "C6") (pin "2") (pinfunction "2_2") (pintype "passive"))
      (node (ref "C8") (pin "2") (pinfunction "2_2") (pintype "passive"))
      (node (ref "C9") (pin "2") (pinfunction "2_2") (pintype "passive"))
      (node (ref "D1") (pin "A") (pinfunction "A_A") (pintype "passive"))
      (node (ref "D2") (pin "A") (pinfunction "A_A") (pintype "passive"))
      (node (ref "D6") (pin "A") (pinfunction "A_A") (pintype "passive"))
      (node (ref "D8") (pin "A") (pinfunction "A_A") (pintype "passive"))
      (node (ref "EARTH1") (pin "1") (pinfunction "P_1") (pintype "passive"))
      (node (ref "EARTH2") (pin "1") (pinfunction "P_1") (pintype "passive"))
      (node (ref "R11") (pin "1") (pinfunction "1_1") (pintype "passive"))
      (node (ref "R13") (pin "1") (pinfunction "1_1") (pintype "passive"))
      (node (ref "R14") (pin "1") (pinfunction "1_1") (pintype "passive"))
      (node (ref "R24") (pin "1") (pinfunction "1_1") (pintype "passive"))
      (node (ref "R27") (pin "1") (pinfunction "1_1") (pintype "passive"))
      (node (ref "R28") (pin "1") (pinfunction "1_1") (pintype "passive"))
      (node (ref "R30") (pin "1") (pinfunction "1_1") (pintype "passive"))
      (node (ref "R47") (pin "1") (pinfunction "1_1") (pintype "passive"))
      (node (ref "U$11") (pin "3") (pinfunction "S_3") (pintype "passive"))
      (node (ref "U$12") (pin "2") (pinfunction "2_2") (pintype "passive"))
      (node (ref "U$12") (pin "3") (pinfunction "2_3") (pintype "passive"))
      (node (ref "U$12") (pin "4") (pinfunction "2_4") (pintype "passive"))
      (node (ref "U$12") (pin "5") (pinfunction "2_5") (pintype "passive"))
      (node (ref "U$13") (pin "2") (pinfunction "2_2") (pintype "passive"))
      (node (ref "U$13") (pin "3") (pinfunction "2_3") (pintype "passive"))
      (node (ref "U$13") (pin "4") (pinfunction "2_4") (pintype "passive"))
      (node (ref "U$13") (pin "5") (pinfunction "2_5") (pintype "passive"))
      (node (ref "U$8") (pin "3") (pinfunction "S_3") (pintype "passive"))
      (node (ref "U1") (pin "4") (pinfunction "GND_4") (pintype "power_in"))
      (node (ref "U1") (pin "9") (pinfunction "VSSB_9") (pintype "power_in"))
      (node (ref "U2") (pin "4") (pinfunction "GND_4") (pintype "power_in"))
      (node (ref "U2") (pin "9") (pinfunction "VSSB_9") (pintype "power_in"))
    )
    (net (code "76") (name "unconnected-(U1-NC-Pad13)") (class "Default")
      (node (ref "U1") (pin "13") (pinfunction "NC_13") (pintype "passive"))
    )
    (net (code "77") (name "unconnected-(U1-NC_2-Pad7)") (class "Default")
      (node (ref "U1") (pin "7") (pinfunction "NC_2_7") (pintype "passive"))
    )
    (net (code "78") (name "unconnected-(U1-NC_3-Pad12)") (class "Default")
      (node (ref "U1") (pin "12") (pinfunction "NC_3_12") (pintype "passive"))
    )
    (net (code "79") (name "unconnected-(U2-NC-Pad13)") (class "Default")
      (node (ref "U2") (pin "13") (pinfunction "NC_13") (pintype "passive"))
    )
    (net (code "80") (name "unconnected-(U2-NC_2-Pad7)") (class "Default")
      (node (ref "U2") (pin "7") (pinfunction "NC_2_7") (pintype "passive"))
    )
    (net (code "81") (name "unconnected-(U2-NC_3-Pad12)") (class "Default")
      (node (ref "U2") (pin "12") (pinfunction "NC_3_12") (pintype "passive"))
    )
  )
)
